# BOTTOM_v40.net
KiCad netlist of a schematic drawn in Altium Designer
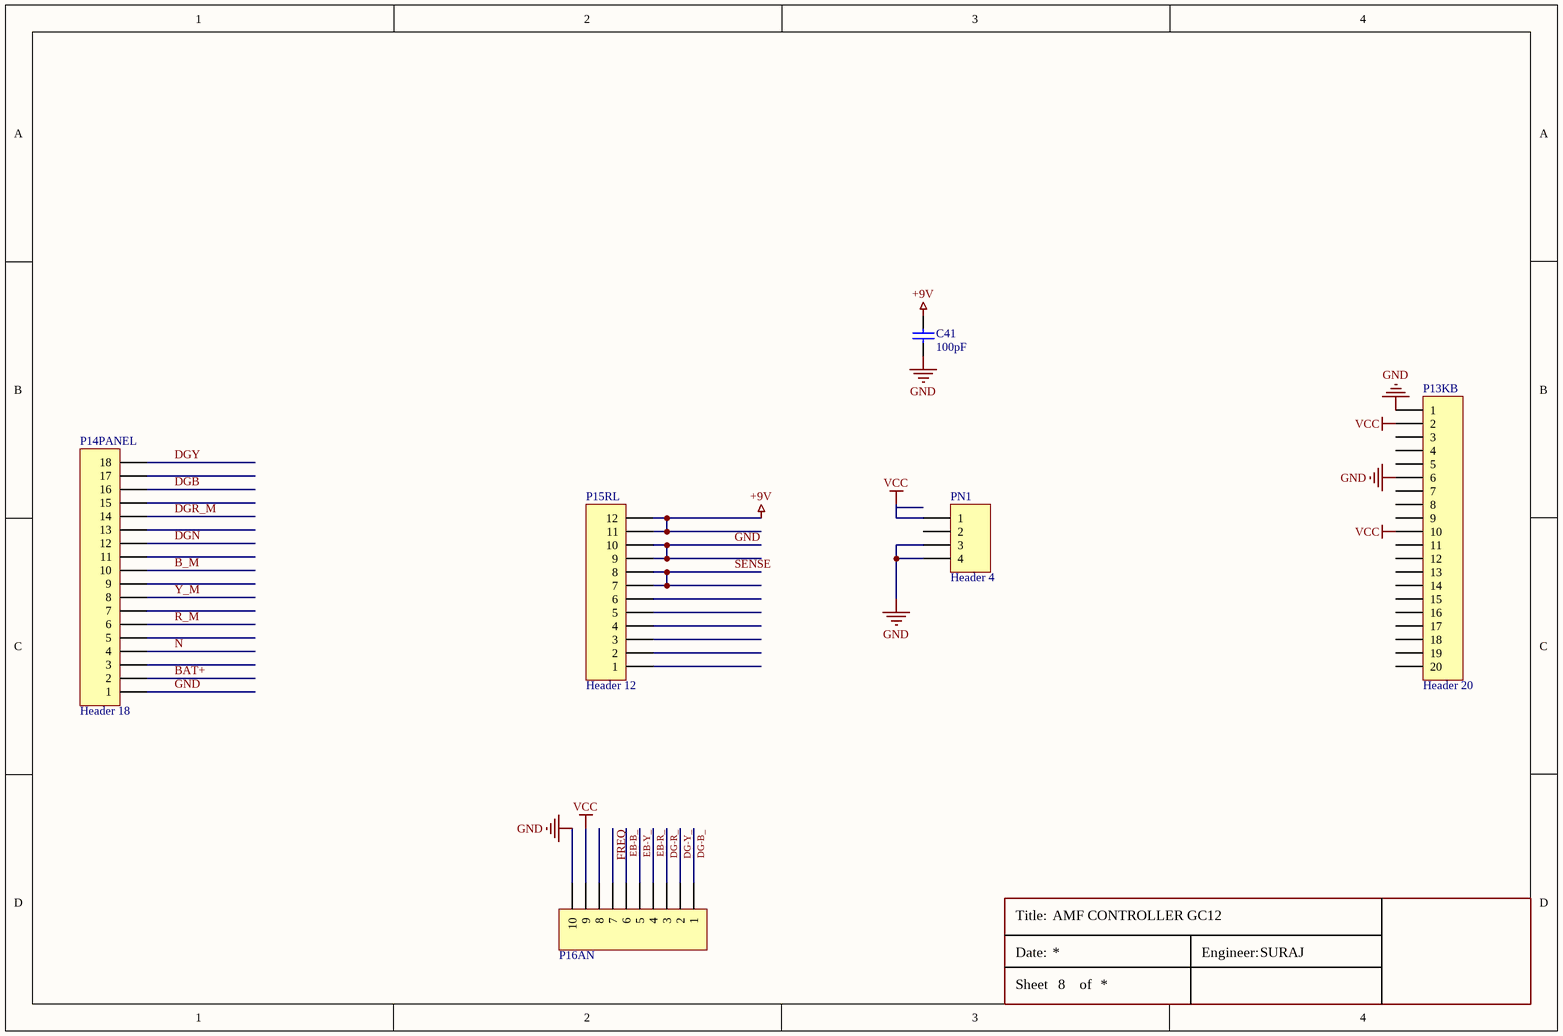
[diagram p0: BOTTOM_v40.SchDoc]

(export (version "E")
  (design (tool "Eeschema 10.0.6"))
  (components
    (comp (ref "C41")
      (value "100pF")
      (footprint "C1206")
      (description "Capacitor")
      (fields (field (name "Comment") ".1uF 1206") (field (name "PUBLISHER") "Altium Limited"))
      (libsource (lib "Miscellaneous Devices") (part "Cap"))
    )
    (comp (ref "P13KB")
      (value "Header 20")
      (footprint "HDR1X20_BURGE_F")
      (description "Header, 20-Pin")
      (fields (field (name "PUBLISHER") "Altium Limited"))
      (libsource (lib "Miscellaneous Connectors") (part "Header 20"))
    )
    (comp (ref "P14PANEL")
      (value "Header 18")
      (footprint "HDR1X18_BURGE_F")
      (description "Header, 18-Pin")
      (fields (field (name "PUBLISHER") "Altium Limited"))
      (libsource (lib "Miscellaneous Connectors") (part "Header 18"))
    )
    (comp (ref "P15RL")
      (value "Header 12")
      (footprint "HDR1X12_BURGE_F")
      (description "Header, 12-Pin")
      (fields (field (name "PUBLISHER") "Altium Limited"))
      (libsource (lib "Miscellaneous Connectors") (part "Header 12"))
    )
    (comp (ref "P16AN")
      (value "Header 10")
      (footprint "HDR1X10_BURGE_F")
      (description "Header, 10-Pin")
      (fields (field (name "PUBLISHER") "Altium Limited"))
      (libsource (lib "Miscellaneous Connectors") (part "Header 10"))
    )
    (comp (ref "PN1")
      (value "Header 4")
      (footprint "HDR1X4_BURGE_F")
      (description "Header, 4-Pin")
      (fields (field (name "PUBLISHER") "Altium Limited"))
      (libsource (lib "Miscellaneous Connectors") (part "Header 4"))
    )
  )
  (nets
    (net (code "1") (name "+9V") (class "Default")
      (node (ref "C41") (pin "2") (pinfunction "2_2") (pintype "passive"))
      (node (ref "P15RL") (pin "11") (pinfunction "11_11") (pintype "passive"))
      (node (ref "P15RL") (pin "12") (pinfunction "12_12") (pintype "passive"))
    )
    (net (code "2") (name "/BAT+") (class "Default")
      (node (ref "P14PANEL") (pin "2") (pinfunction "2_2") (pintype "passive"))
    )
    (net (code "3") (name "/B_M") (class "Default")
      (node (ref "P14PANEL") (pin "10") (pinfunction "10_10") (pintype "passive"))
    )
    (net (code "4") (name "/DG-B_") (class "Default")
      (node (ref "P16AN") (pin "1") (pinfunction "1_1") (pintype "passive"))
    )
    (net (code "5") (name "/DG-R_") (class "Default")
      (node (ref "P16AN") (pin "3") (pinfunction "3_3") (pintype "passive"))
    )
    (net (code "6") (name "/DG-Y_") (class "Default")
      (node (ref "P16AN") (pin "2") (pinfunction "2_2") (pintype "passive"))
    )
    (net (code "7") (name "/DGB") (class "Default")
      (node (ref "P14PANEL") (pin "16") (pinfunction "16_16") (pintype "passive"))
    )
    (net (code "8") (name "/DGN") (class "Default")
      (node (ref "P14PANEL") (pin "12") (pinfunction "12_12") (pintype "passive"))
    )
    (net (code "9") (name "/DGR_M") (class "Default")
      (node (ref "P14PANEL") (pin "14") (pinfunction "14_14") (pintype "passive"))
    )
    (net (code "10") (name "/DGY") (class "Default")
      (node (ref "P14PANEL") (pin "18") (pinfunction "18_18") (pintype "passive"))
    )
    (net (code "11") (name "/EB-B_") (class "Default")
      (node (ref "P16AN") (pin "6") (pinfunction "6_6") (pintype "passive"))
    )
    (net (code "12") (name "/EB-R_") (class "Default")
      (node (ref "P16AN") (pin "4") (pinfunction "4_4") (pintype "passive"))
    )
    (net (code "13") (name "/EB-Y_") (class "Default")
      (node (ref "P16AN") (pin "5") (pinfunction "5_5") (pintype "passive"))
    )
    (net (code "14") (name "/FREQ") (class "Default")
      (node (ref "P16AN") (pin "7") (pinfunction "7_7") (pintype "passive"))
    )
    (net (code "15") (name "/N") (class "Default")
      (node (ref "P14PANEL") (pin "4") (pinfunction "4_4") (pintype "passive"))
    )
    (net (code "16") (name "/R_M") (class "Default")
      (node (ref "P14PANEL") (pin "6") (pinfunction "6_6") (pintype "passive"))
    )
    (net (code "17") (name "/SENSE") (class "Default")
      (node (ref "P15RL") (pin "7") (pinfunction "7_7") (pintype "passive"))
      (node (ref "P15RL") (pin "8") (pinfunction "8_8") (pintype "passive"))
    )
    (net (code "18") (name "/Y_M") (class "Default")
      (node (ref "P14PANEL") (pin "8") (pinfunction "8_8") (pintype "passive"))
    )
    (net (code "19") (name "GND") (class "Default")
      (node (ref "C41") (pin "1") (pinfunction "1_1") (pintype "passive"))
      (node (ref "P13KB") (pin "1") (pinfunction "1_1") (pintype "passive"))
      (node (ref "P13KB") (pin "6") (pinfunction "6_6") (pintype "passive"))
      (node (ref "P14PANEL") (pin "1") (pinfunction "1_1") (pintype "passive"))
      (node (ref "P15RL") (pin "10") (pinfunction "10_10") (pintype "passive"))
      (node (ref "P15RL") (pin "9") (pinfunction "9_9") (pintype "passive"))
      (node (ref "P16AN") (pin "10") (pinfunction "10_10") (pintype "passive"))
      (node (ref "PN1") (pin "3") (pinfunction "3_3") (pintype "passive"))
      (node (ref "PN1") (pin "4") (pinfunction "4_4") (pintype "passive"))
    )
    (net (code "20") (name "VCC") (class "Default")
      (node (ref "P13KB") (pin "10") (pinfunction "10_10") (pintype "passive"))
      (node (ref "P13KB") (pin "2") (pinfunction "2_2") (pintype "passive"))
      (node (ref "P16AN") (pin "9") (pinfunction "9_9") (pintype "passive"))
      (node (ref "PN1") (pin "1") (pinfunction "1_1") (pintype "passive"))
    )
    (net (code "21") (name "unconnected-(P13KB-Pad3)") (class "Default")
      (node (ref "P13KB") (pin "3") (pinfunction "3_3") (pintype "passive"))
    )
    (net (code "22") (name "unconnected-(P13KB-Pad4)") (class "Default")
      (node (ref "P13KB") (pin "4") (pinfunction "4_4") (pintype "passive"))
    )
    (net (code "23") (name "unconnected-(P13KB-Pad5)") (class "Default")
      (node (ref "P13KB") (pin "5") (pinfunction "5_5") (pintype "passive"))
    )
    (net (code "24") (name "unconnected-(P13KB-Pad7)") (class "Default")
      (node (ref "P13KB") (pin "7") (pinfunction "7_7") (pintype "passive"))
    )
    (net (code "25") (name "unconnected-(P13KB-Pad8)") (class "Default")
      (node (ref "P13KB") (pin "8") (pinfunction "8_8") (pintype "passive"))
    )
    (net (code "26") (name "unconnected-(P13KB-Pad9)") (class "Default")
      (node (ref "P13KB") (pin "9") (pinfunction "9_9") (pintype "passive"))
    )
    (net (code "27") (name "unconnected-(P13KB-Pad11)") (class "Default")
      (node (ref "P13KB") (pin "11") (pinfunction "11_11") (pintype "passive"))
    )
    (net (code "28") (name "unconnected-(P13KB-Pad12)") (class "Default")
      (node (ref "P13KB") (pin "12") (pinfunction "12_12") (pintype "passive"))
    )
    (net (code "29") (name "unconnected-(P13KB-Pad13)") (class "Default")
      (node (ref "P13KB") (pin "13") (pinfunction "13_13") (pintype "passive"))
    )
    (net (code "30") (name "unconnected-(P13KB-Pad14)") (class "Default")
      (node (ref "P13KB") (pin "14") (pinfunction "14_14") (pintype "passive"))
    )
    (net (code "31") (name "unconnected-(P13KB-Pad15)") (class "Default")
      (node (ref "P13KB") (pin "15") (pinfunction "15_15") (pintype "passive"))
    )
    (net (code "32") (name "unconnected-(P13KB-Pad16)") (class "Default")
      (node (ref "P13KB") (pin "16") (pinfunction "16_16") (pintype "passive"))
    )
    (net (code "33") (name "unconnected-(P13KB-Pad17)") (class "Default")
      (node (ref "P13KB") (pin "17") (pinfunction "17_17") (pintype "passive"))
    )
    (net (code "34") (name "unconnected-(P13KB-Pad18)") (class "Default")
      (node (ref "P13KB") (pin "18") (pinfunction "18_18") (pintype "passive"))
    )
    (net (code "35") (name "unconnected-(P13KB-Pad19)") (class "Default")
      (node (ref "P13KB") (pin "19") (pinfunction "19_19") (pintype "passive"))
    )
    (net (code "36") (name "unconnected-(P13KB-Pad20)") (class "Default")
      (node (ref "P13KB") (pin "20") (pinfunction "20_20") (pintype "passive"))
    )
    (net (code "37") (name "unconnected-(P14PANEL-Pad3)") (class "Default")
      (node (ref "P14PANEL") (pin "3") (pinfunction "3_3") (pintype "passive"))
    )
    (net (code "38") (name "unconnected-(P14PANEL-Pad5)") (class "Default")
      (node (ref "P14PANEL") (pin "5") (pinfunction "5_5") (pintype "passive"))
    )
    (net (code "39") (name "unconnected-(P14PANEL-Pad7)") (class "Default")
      (node (ref "P14PANEL") (pin "7") (pinfunction "7_7") (pintype "passive"))
    )
    (net (code "40") (name "unconnected-(P14PANEL-Pad9)") (class "Default")
      (node (ref "P14PANEL") (pin "9") (pinfunction "9_9") (pintype "passive"))
    )
    (net (code "41") (name "unconnected-(P14PANEL-Pad11)") (class "Default")
      (node (ref "P14PANEL") (pin "11") (pinfunction "11_11") (pintype "passive"))
    )
    (net (code "42") (name "unconnected-(P14PANEL-Pad13)") (class "Default")
      (node (ref "P14PANEL") (pin "13") (pinfunction "13_13") (pintype "passive"))
    )
    (net (code "43") (name "unconnected-(P14PANEL-Pad15)") (class "Default")
      (node (ref "P14PANEL") (pin "15") (pinfunction "15_15") (pintype "passive"))
    )
    (net (code "44") (name "unconnected-(P14PANEL-Pad17)") (class "Default")
      (node (ref "P14PANEL") (pin "17") (pinfunction "17_17") (pintype "passive"))
    )
    (net (code "45") (name "unconnected-(P15RL-Pad1)") (class "Default")
      (node (ref "P15RL") (pin "1") (pinfunction "1_1") (pintype "passive"))
    )
    (net (code "46") (name "unconnected-(P15RL-Pad2)") (class "Default")
      (node (ref "P15RL") (pin "2") (pinfunction "2_2") (pintype "passive"))
    )
    (net (code "47") (name "unconnected-(P15RL-Pad3)") (class "Default")
      (node (ref "P15RL") (pin "3") (pinfunction "3_3") (pintype "passive"))
    )
    (net (code "48") (name "unconnected-(P15RL-Pad4)") (class "Default")
      (node (ref "P15RL") (pin "4") (pinfunction "4_4") (pintype "passive"))
    )
    (net (code "49") (name "unconnected-(P15RL-Pad5)") (class "Default")
      (node (ref "P15RL") (pin "5") (pinfunction "5_5") (pintype "passive"))
    )
    (net (code "50") (name "unconnected-(P15RL-Pad6)") (class "Default")
      (node (ref "P15RL") (pin "6") (pinfunction "6_6") (pintype "passive"))
    )
    (net (code "51") (name "unconnected-(P16AN-Pad8)") (class "Default")
      (node (ref "P16AN") (pin "8") (pinfunction "8_8") (pintype "passive"))
    )
    (net (code "52") (name "unconnected-(PN1-Pad2)") (class "Default")
      (node (ref "PN1") (pin "2") (pinfunction "2_2") (pintype "passive"))
    )
  )
)
